# umodular_pot8.net
KiCad netlist of a schematic drawn in EAGLE
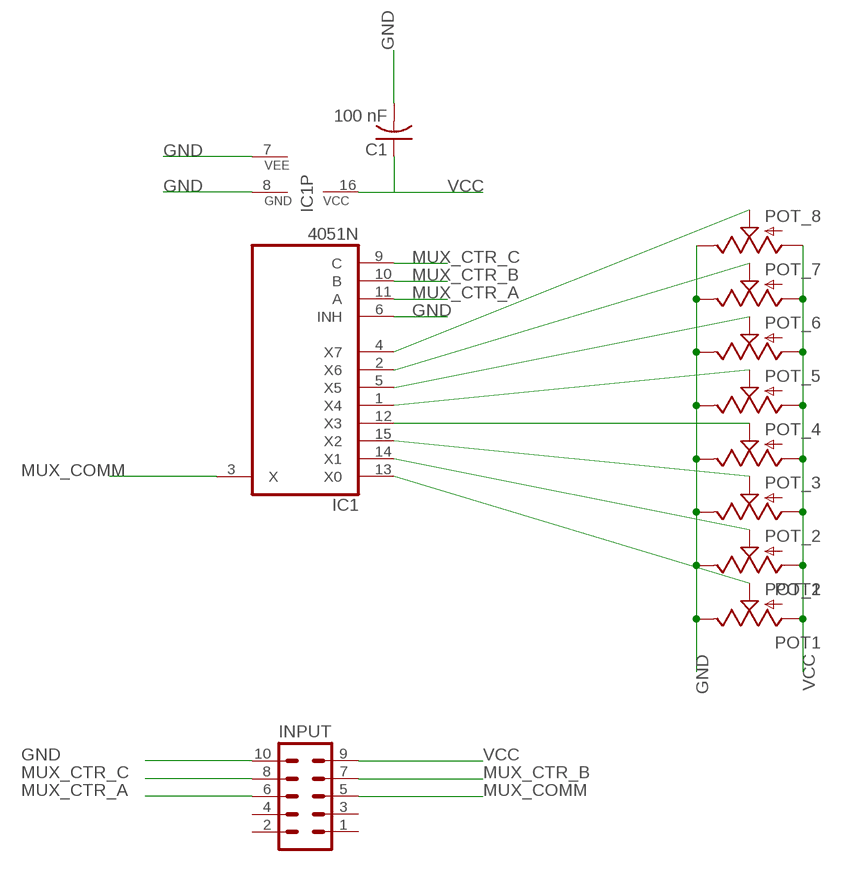
[diagram p0: schematic, sheet 1]

(export (version "E")
  (design (tool "Eeschema 10.0.6"))
  (components
    (comp (ref "C1")
      (value "100 nF")
      (footprint "eagle-import:C050-024X044")
      (libsource (lib "eagle-import") (part "C-US050-024X044"))
    )
    (comp (ref "IC1")
      (value "4051N")
      (footprint "eagle-import:DIL16")
      (libsource (lib "eagle-import") (part "4051N"))
    )
    (comp (ref "INPUT")
      (value "MA05-2")
      (footprint "eagle-import:MA05-2")
      (libsource (lib "eagle-import") (part "MA05-2"))
    )
    (comp (ref "POT_1")
      (value "POT1")
      (footprint "eagle-import:ALPS_POT")
      (libsource (lib "eagle-import") (part "POT"))
    )
    (comp (ref "POT_2")
      (value "POT2")
      (footprint "eagle-import:ALPS_POT")
      (libsource (lib "eagle-import") (part "POT"))
    )
    (comp (ref "POT_3")
      (value "POT")
      (footprint "eagle-import:ALPS_POT")
      (libsource (lib "eagle-import") (part "POT"))
    )
    (comp (ref "POT_4")
      (value "POT")
      (footprint "eagle-import:ALPS_POT")
      (libsource (lib "eagle-import") (part "POT"))
    )
    (comp (ref "POT_5")
      (value "POT")
      (footprint "eagle-import:ALPS_POT")
      (libsource (lib "eagle-import") (part "POT"))
    )
    (comp (ref "POT_6")
      (value "POT")
      (footprint "eagle-import:ALPS_POT")
      (libsource (lib "eagle-import") (part "POT"))
    )
    (comp (ref "POT_7")
      (value "POT")
      (footprint "eagle-import:ALPS_POT")
      (libsource (lib "eagle-import") (part "POT"))
    )
    (comp (ref "POT_8")
      (value "POT")
      (footprint "eagle-import:ALPS_POT")
      (libsource (lib "eagle-import") (part "POT"))
    )
  )
  (nets
    (net (code "1") (name "/GND") (class "Default")
      (node (ref "C1") (pin "2") (pinfunction "2_2") (pintype "passive"))
      (node (ref "IC1") (pin "6") (pinfunction "INH_6") (pintype "input"))
      (node (ref "IC1") (pin "7") (pinfunction "VEE_7") (pintype "power_in"))
      (node (ref "IC1") (pin "8") (pinfunction "GND_8") (pintype "power_in"))
      (node (ref "INPUT") (pin "10") (pinfunction "10_10") (pintype "passive"))
      (node (ref "POT_1") (pin "P$1") (pinfunction "E_P$1") (pintype "passive"))
      (node (ref "POT_2") (pin "P$1") (pinfunction "E_P$1") (pintype "passive"))
      (node (ref "POT_3") (pin "P$1") (pinfunction "E_P$1") (pintype "passive"))
      (node (ref "POT_4") (pin "P$1") (pinfunction "E_P$1") (pintype "passive"))
      (node (ref "POT_5") (pin "P$1") (pinfunction "E_P$1") (pintype "passive"))
      (node (ref "POT_6") (pin "P$1") (pinfunction "E_P$1") (pintype "passive"))
      (node (ref "POT_7") (pin "P$1") (pinfunction "E_P$1") (pintype "passive"))
      (node (ref "POT_8") (pin "P$1") (pinfunction "E_P$1") (pintype "passive"))
    )
    (net (code "2") (name "/MUX_COMM") (class "Default")
      (node (ref "IC1") (pin "3") (pinfunction "X_3") (pintype "bidirectional"))
      (node (ref "INPUT") (pin "5") (pinfunction "5_5") (pintype "passive"))
    )
    (net (code "3") (name "/MUX_CTR_A") (class "Default")
      (node (ref "IC1") (pin "11") (pinfunction "A_11") (pintype "input"))
      (node (ref "INPUT") (pin "6") (pinfunction "6_6") (pintype "passive"))
    )
    (net (code "4") (name "/MUX_CTR_B") (class "Default")
      (node (ref "IC1") (pin "10") (pinfunction "B_10") (pintype "input"))
      (node (ref "INPUT") (pin "7") (pinfunction "7_7") (pintype "passive"))
    )
    (net (code "5") (name "/MUX_CTR_C") (class "Default")
      (node (ref "IC1") (pin "9") (pinfunction "C_9") (pintype "input"))
      (node (ref "INPUT") (pin "8") (pinfunction "8_8") (pintype "passive"))
    )
    (net (code "6") (name "/VCC") (class "Default")
      (node (ref "C1") (pin "1") (pinfunction "1_1") (pintype "passive"))
      (node (ref "IC1") (pin "16") (pinfunction "VCC_16") (pintype "power_in"))
      (node (ref "INPUT") (pin "9") (pinfunction "9_9") (pintype "passive"))
      (node (ref "POT_1") (pin "P$3") (pinfunction "A_P$3") (pintype "passive"))
      (node (ref "POT_2") (pin "P$3") (pinfunction "A_P$3") (pintype "passive"))
      (node (ref "POT_3") (pin "P$3") (pinfunction "A_P$3") (pintype "passive"))
      (node (ref "POT_4") (pin "P$3") (pinfunction "A_P$3") (pintype "passive"))
      (node (ref "POT_5") (pin "P$3") (pinfunction "A_P$3") (pintype "passive"))
      (node (ref "POT_6") (pin "P$3") (pinfunction "A_P$3") (pintype "passive"))
      (node (ref "POT_7") (pin "P$3") (pinfunction "A_P$3") (pintype "passive"))
      (node (ref "POT_8") (pin "P$3") (pinfunction "A_P$3") (pintype "passive"))
    )
    (net (code "7") (name "Net-(IC1A-X0)") (class "Default")
      (node (ref "IC1") (pin "13") (pinfunction "X0_13") (pintype "bidirectional"))
      (node (ref "POT_1") (pin "P$2") (pinfunction "S_P$2") (pintype "passive"))
    )
    (net (code "8") (name "Net-(IC1A-X1)") (class "Default")
      (node (ref "IC1") (pin "14") (pinfunction "X1_14") (pintype "bidirectional"))
      (node (ref "POT_2") (pin "P$2") (pinfunction "S_P$2") (pintype "passive"))
    )
    (net (code "9") (name "Net-(IC1A-X2)") (class "Default")
      (node (ref "IC1") (pin "15") (pinfunction "X2_15") (pintype "bidirectional"))
      (node (ref "POT_3") (pin "P$2") (pinfunction "S_P$2") (pintype "passive"))
    )
    (net (code "10") (name "Net-(IC1A-X3)") (class "Default")
      (node (ref "IC1") (pin "12") (pinfunction "X3_12") (pintype "bidirectional"))
      (node (ref "POT_4") (pin "P$2") (pinfunction "S_P$2") (pintype "passive"))
    )
    (net (code "11") (name "Net-(IC1A-X4)") (class "Default")
      (node (ref "IC1") (pin "1") (pinfunction "X4_1") (pintype "bidirectional"))
      (node (ref "POT_5") (pin "P$2") (pinfunction "S_P$2") (pintype "passive"))
    )
    (net (code "12") (name "Net-(IC1A-X5)") (class "Default")
      (node (ref "IC1") (pin "5") (pinfunction "X5_5") (pintype "bidirectional"))
      (node (ref "POT_6") (pin "P$2") (pinfunction "S_P$2") (pintype "passive"))
    )
    (net (code "13") (name "Net-(IC1A-X6)") (class "Default")
      (node (ref "IC1") (pin "2") (pinfunction "X6_2") (pintype "bidirectional"))
      (node (ref "POT_7") (pin "P$2") (pinfunction "S_P$2") (pintype "passive"))
    )
    (net (code "14") (name "Net-(IC1A-X7)") (class "Default")
      (node (ref "IC1") (pin "4") (pinfunction "X7_4") (pintype "bidirectional"))
      (node (ref "POT_8") (pin "P$2") (pinfunction "S_P$2") (pintype "passive"))
    )
    (net (code "15") (name "unconnected-(INPUT-Pad1)") (class "Default")
      (node (ref "INPUT") (pin "1") (pinfunction "1_1") (pintype "passive"))
    )
    (net (code "16") (name "unconnected-(INPUT-Pad2)") (class "Default")
      (node (ref "INPUT") (pin "2") (pinfunction "2_2") (pintype "passive"))
    )
    (net (code "17") (name "unconnected-(INPUT-Pad3)") (class "Default")
      (node (ref "INPUT") (pin "3") (pinfunction "3_3") (pintype "passive"))
    )
    (net (code "18") (name "unconnected-(INPUT-Pad4)") (class "Default")
      (node (ref "INPUT") (pin "4") (pinfunction "4_4") (pintype "passive"))
    )
  )
)
